# Supplies.net
KiCad netlist of a schematic drawn in Altium Designer
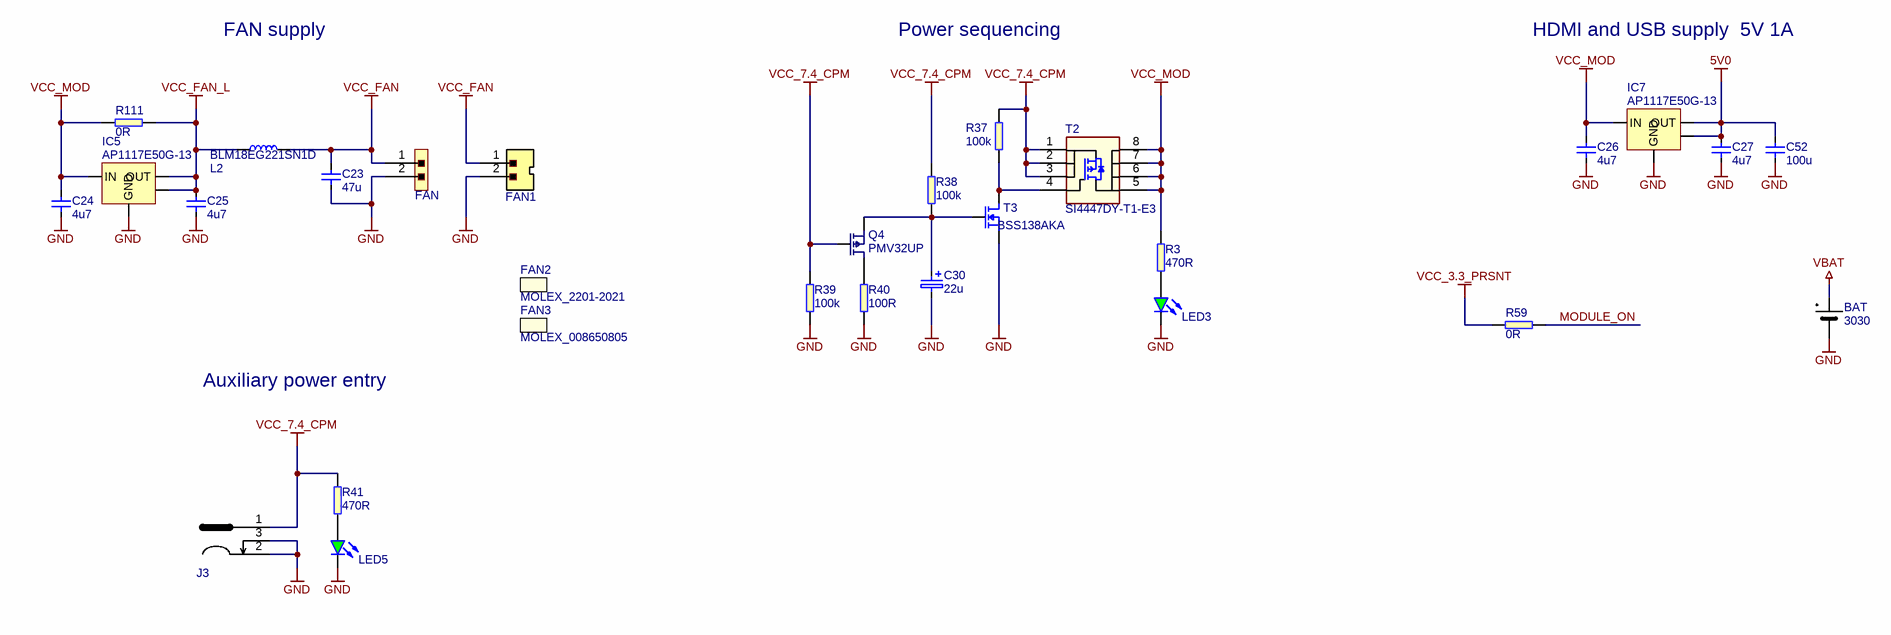
[diagram p0: Supplies.SchDoc]

(export (version "E")
  (design (tool "Eeschema 10.0.6"))
  (components
    (comp (ref "BAT")
      (value "3030")
      (footprint "KEYSTONE_CR1025")
      (description "SMT holder for  CR1025 battery")
      (fields (field (name "MANUFACTURER") "Keystone") (field (name "PART NUMBER") "Keystone_CR1025"))
      (libsource (lib "US-Plus-CPM") (part "battery"))
    )
    (comp (ref "C23")
      (value "47u")
      (footprint "1206")
      (description "MLCC SMT Capacitor 47uF 1206")
      (fields (field (name "PART NUMBER") "C_47u_1206") (field (name "MANUFACTURER") "MURATA"))
      (libsource (lib "US-Plus-CPM") (part "C"))
    )
    (comp (ref "C24")
      (value "4u7")
      (footprint "0603")
      (description "MLCC SMT Capacitor 4u7F 0603")
      (fields (field (name "PART NUMBER") "C_4u7_0603") (field (name "MANUFACTURER") "MULTICOMP"))
      (libsource (lib "US-Plus-CPM") (part "C"))
    )
    (comp (ref "C25")
      (value "4u7")
      (footprint "0603")
      (description "MLCC SMT Capacitor 4u7F 0603")
      (fields (field (name "PART NUMBER") "C_4u7_0603") (field (name "MANUFACTURER") "MULTICOMP"))
      (libsource (lib "US-Plus-CPM") (part "C"))
    )
    (comp (ref "C26")
      (value "4u7")
      (footprint "0603")
      (description "MLCC SMT Capacitor 4u7F 0603")
      (fields (field (name "PART NUMBER") "C_4u7_0603") (field (name "MANUFACTURER") "MULTICOMP"))
      (libsource (lib "US-Plus-CPM") (part "C"))
    )
    (comp (ref "C27")
      (value "4u7")
      (footprint "0603")
      (description "MLCC SMT Capacitor 4u7F 0603")
      (fields (field (name "PART NUMBER") "C_4u7_0603") (field (name "MANUFACTURER") "MULTICOMP"))
      (libsource (lib "US-Plus-CPM") (part "C"))
    )
    (comp (ref "C30")
      (value "22u")
      (footprint "KEMET_C")
      (description "Tantalum SMT Capacitor 22uF Case KEMET_C")
      (fields (field (name "PART NUMBER") "C_22u_KEMET_C") (field (name "MANUFACTURER") "KEMET"))
      (libsource (lib "US-Plus-CPM") (part "CPol"))
    )
    (comp (ref "C52")
      (value "100u")
      (footprint "0805")
      (description "MLCC SMT Capacitor 100uF 0805")
      (fields (field (name "PART NUMBER") "C_100u_0805") (field (name "MANUFACTURER") "MURATA"))
      (libsource (lib "") (part "C_1"))
    )
    (comp (ref "FAN")
      (value "*")
      (footprint "HEADER_1X2_male 2.54mm Angle")
      (description "1x2 pinhead male angle")
      (fields (field (name "PART NUMBER") "HEADER_1X2_male_angle"))
      (libsource (lib "US-Plus-CPM") (part "HEADER_1X2_male_angle"))
    )
    (comp (ref "FAN1")
      (value "MX-22-23-2021")
      (footprint "molex_2223-2021")
      (description "Pinhead connector with key")
      (fields (field (name "PART NUMBER") "molex_2223-2021") (field (name "MANUFACTURER") "Molex"))
      (libsource (lib "US-Plus-CPM") (part "molex_2223-2021"))
    )
    (comp (ref "FAN2")
      (value "MOLEX_2201-2021")
      (description "KK 254 Crimp Housing 2 circuits")
      (fields (field (name "MANUFACTURER") "MOLEX"))
      (libsource (lib "US-Plus-CPM") (part "GENERIC_BOM_ONLY"))
    )
    (comp (ref "FAN3")
      (value "MOLEX_008650805")
      (description "conn term female 22-30 awg tin")
      (fields (field (name "MANUFACTURER") "MOLEX"))
      (libsource (lib "US-Plus-CPM") (part "GENERIC_BOM_ONLY"))
    )
    (comp (ref "IC5")
      (value "AP1117E50G-13")
      (footprint "PCB:SOT223")
      (description "LDO, 2V/5.5V, 1A, 5V,  SOT223")
      (fields (field (name "MANUFACTURER") "Diodes"))
      (libsource (lib "US-Plus-CPM") (part "xx1117"))
    )
    (comp (ref "IC7")
      (value "AP1117E50G-13")
      (footprint "SOT223")
      (description "LDO, 2V/5.5V, 1A, 5V,  SOT223")
      (fields (field (name "MANUFACTURER") "Diodes"))
      (libsource (lib "US-Plus-CPM") (part "xx1117"))
    )
    (comp (ref "J3")
      (value "694106106102")
      (footprint "694106106102")
      (description "DC Power Jack Right Angled SMT Ø6.4 with 4 soldering pads & pegs WR-DC")
      (fields (field (name "PART NUMBER") "WE-694106106102") (field (name "MANUFACTURER") "WURTH ELEKTRONIK"))
      (libsource (lib "US-Plus-CPM") (part "DC_SOCKET_2"))
    )
    (comp (ref "L2")
      (value "BLM18EG221SN1D")
      (footprint "0603")
      (description "MURATA 	BLM18EG221SN1D  FERRITE BEAD, 0.05OHM, 2A, 0603")
      (fields (field (name "MANUFACTURER") "MURATA"))
      (libsource (lib "US-Plus-CPM") (part "Inductor SMT"))
    )
    (comp (ref "LED3")
      (value "KPT-1608SGC")
      (footprint "LED0603")
      (description "LED Green 0603 case")
      (fields (field (name "PART NUMBER") "LED_G") (field (name "MANUFACTURER") "KINGBRIGHT"))
      (libsource (lib "US-Plus-CPM") (part "LED"))
    )
    (comp (ref "LED5")
      (value "KPT-1608SGC")
      (footprint "LED0603")
      (description "LED Green 0603 case")
      (fields (field (name "PART NUMBER") "LED_G") (field (name "MANUFACTURER") "KINGBRIGHT"))
      (libsource (lib "US-Plus-CPM") (part "LED"))
    )
    (comp (ref "Q4")
      (value "PMV32UP")
      (footprint "SOT-23")
      (description "P CH, 20V, 4A")
      (fields (field (name "MANUFACTURER") "NXP"))
      (libsource (lib "US-Plus-CPM") (part "PMOS"))
    )
    (comp (ref "R3")
      (value "470R")
      (footprint "0603")
      (description "SMT Resistor 470R 0603")
      (fields (field (name "PART NUMBER") "R_470R_0603") (field (name "MANUFACTURER") "BOURNS"))
      (libsource (lib "US-Plus-CPM") (part "R"))
    )
    (comp (ref "R37")
      (value "100k")
      (footprint "0603")
      (description "SMT Resistor 100k 0603")
      (fields (field (name "PART NUMBER") "R_100k_0603") (field (name "MANUFACTURER") "BOURNS"))
      (libsource (lib "US-Plus-CPM") (part "R"))
    )
    (comp (ref "R38")
      (value "100k")
      (footprint "0603")
      (description "SMT Resistor 100k 0603")
      (fields (field (name "PART NUMBER") "R_100k_0603") (field (name "MANUFACTURER") "BOURNS"))
      (libsource (lib "US-Plus-CPM") (part "R"))
    )
    (comp (ref "R39")
      (value "100k")
      (footprint "0603")
      (description "SMT Resistor 100k 0603")
      (fields (field (name "PART NUMBER") "R_100k_0603") (field (name "MANUFACTURER") "BOURNS"))
      (libsource (lib "US-Plus-CPM") (part "R"))
    )
    (comp (ref "R40")
      (value "100R")
      (footprint "0603")
      (description "SMT Resistor 100R 0603")
      (fields (field (name "PART NUMBER") "R_100R_0603") (field (name "MANUFACTURER") "MULTICOMP"))
      (libsource (lib "US-Plus-CPM") (part "R"))
    )
    (comp (ref "R41")
      (value "470R")
      (footprint "0603")
      (description "SMT Resistor 470R 0603")
      (fields (field (name "PART NUMBER") "R_470R_0603") (field (name "MANUFACTURER") "BOURNS"))
      (libsource (lib "US-Plus-CPM") (part "R"))
    )
    (comp (ref "R59")
      (value "0R")
      (footprint "0603")
      (description "SMT Resistor 0R 0603")
      (fields (field (name "PART NUMBER") "R_0R_0603") (field (name "MANUFACTURER") "BOURNS"))
      (libsource (lib "") (part "R_1"))
    )
    (comp (ref "R111")
      (value "0R")
      (footprint "0603")
      (description "SMT Resistor 0R 0603")
      (fields (field (name "PART NUMBER") "R_0R_0603") (field (name "MANUFACTURER") "BOURNS"))
      (libsource (lib "") (part "R_1"))
    )
    (comp (ref "T2")
      (value "SI4447DY-T1-E3")
      (footprint "SOIC-SN8_M")
      (description "p-channel MOSFET, SI4447DY-T1-E3")
      (fields (field (name "MANUFACTURER") "VISHAY"))
      (libsource (lib "US-Plus-CPM") (part "SI4447DY-T1-E3"))
    )
    (comp (ref "T3")
      (value "BSS138AKA")
      (footprint "SOT-23")
      (description "MOSFET, N CH, 60V, 0.2A")
      (fields (field (name "PART NUMBER") "BSS138") (field (name "MANUFACTURER") "NXP"))
      (libsource (lib "US-Plus-CPM") (part "NMOS"))
    )
  )
  (nets
    (net (code "1") (name "/MODULE_ON") (class "Default") (node (ref "R59") (pin "2") (pintype "passive")))
    (net (code "2") (name "5V0") (class "Default")
      (node (ref "C27") (pin "2") (pinfunction "2_2") (pintype "passive"))
      (node (ref "C52") (pin "2") (pinfunction "2_2") (pintype "passive"))
      (node (ref "IC7") (pin "2") (pinfunction "OUT_2") (pintype "passive"))
      (node (ref "IC7") (pin "4") (pinfunction "OUT_4") (pintype "passive"))
    )
    (net (code "3") (name "GND") (class "Default")
      (node (ref "BAT") (pin "-") (pinfunction "-_-") (pintype "passive"))
      (node (ref "C23") (pin "1") (pinfunction "1_1") (pintype "passive"))
      (node (ref "C24") (pin "1") (pinfunction "1_1") (pintype "passive"))
      (node (ref "C25") (pin "1") (pinfunction "1_1") (pintype "passive"))
      (node (ref "C26") (pin "1") (pinfunction "1_1") (pintype "passive"))
      (node (ref "C27") (pin "1") (pinfunction "1_1") (pintype "passive"))
      (node (ref "C30") (pin "2") (pinfunction "2_2") (pintype "passive"))
      (node (ref "C52") (pin "1") (pinfunction "1_1") (pintype "passive"))
      (node (ref "FAN") (pin "2") (pinfunction "2_2") (pintype "passive"))
      (node (ref "FAN1") (pin "2") (pinfunction "2_2") (pintype "passive"))
      (node (ref "IC5") (pin "1") (pinfunction "GND_1") (pintype "power_in"))
      (node (ref "IC7") (pin "1") (pinfunction "GND_1") (pintype "power_in"))
      (node (ref "J3") (pin "2") (pinfunction "2_2") (pintype "passive"))
      (node (ref "J3") (pin "3") (pinfunction "3_3") (pintype "passive"))
      (node (ref "LED3") (pin "K") (pinfunction "K_K") (pintype "passive"))
      (node (ref "LED5") (pin "K") (pinfunction "K_K") (pintype "passive"))
      (node (ref "R39") (pin "1") (pintype "passive"))
      (node (ref "R40") (pin "1") (pintype "passive"))
      (node (ref "T3") (pin "2") (pinfunction "S_2") (pintype "passive"))
    )
    (net (code "4") (name "Net-(LED3-PadA)") (class "Default")
      (node (ref "LED3") (pin "A") (pinfunction "A_A") (pintype "passive"))
      (node (ref "R3") (pin "1") (pintype "passive"))
    )
    (net (code "5") (name "Net-(LED5-PadA)") (class "Default")
      (node (ref "LED5") (pin "A") (pinfunction "A_A") (pintype "passive"))
      (node (ref "R41") (pin "1") (pintype "passive"))
    )
    (net (code "6") (name "Net-(Q4-D)") (class "Default")
      (node (ref "Q4") (pin "3") (pinfunction "D_3") (pintype "passive"))
      (node (ref "R40") (pin "2") (pintype "passive"))
    )
    (net (code "7") (name "Net-(Q4-S)") (class "Default")
      (node (ref "C30") (pin "1") (pinfunction "1_1") (pintype "passive"))
      (node (ref "Q4") (pin "2") (pinfunction "S_2") (pintype "passive"))
      (node (ref "R38") (pin "1") (pintype "passive"))
      (node (ref "T3") (pin "1") (pinfunction "G_1") (pintype "passive"))
    )
    (net (code "8") (name "Net-(T3-D)") (class "Default")
      (node (ref "R37") (pin "1") (pintype "passive"))
      (node (ref "T2") (pin "4") (pinfunction "4_4") (pintype "passive"))
      (node (ref "T3") (pin "3") (pinfunction "D_3") (pintype "passive"))
    )
    (net (code "9") (name "VBAT") (class "Default")
      (node (ref "BAT") (pin "+") (pinfunction "+_+") (pintype "passive"))
    )
    (net (code "10") (name "VCC_3.3_PRSNT") (class "Default")
      (node (ref "R59") (pin "1") (pintype "passive"))
    )
    (net (code "11") (name "VCC_7.4_CPM") (class "Default")
      (node (ref "J3") (pin "1") (pinfunction "1_1") (pintype "passive"))
      (node (ref "Q4") (pin "1") (pinfunction "G_1") (pintype "passive"))
      (node (ref "R37") (pin "2") (pintype "passive"))
      (node (ref "R38") (pin "2") (pintype "passive"))
      (node (ref "R39") (pin "2") (pintype "passive"))
      (node (ref "R41") (pin "2") (pintype "passive"))
      (node (ref "T2") (pin "1") (pinfunction "1_1") (pintype "passive"))
      (node (ref "T2") (pin "2") (pinfunction "2_2") (pintype "passive"))
      (node (ref "T2") (pin "3") (pinfunction "3_3") (pintype "passive"))
    )
    (net (code "12") (name "VCC_FAN") (class "Default")
      (node (ref "C23") (pin "2") (pinfunction "2_2") (pintype "passive"))
      (node (ref "FAN") (pin "1") (pinfunction "1_1") (pintype "passive"))
      (node (ref "FAN1") (pin "1") (pinfunction "1_1") (pintype "passive"))
      (node (ref "L2") (pin "2") (pintype "passive"))
    )
    (net (code "13") (name "VCC_FAN_L") (class "Default")
      (node (ref "C25") (pin "2") (pinfunction "2_2") (pintype "passive"))
      (node (ref "IC5") (pin "2") (pinfunction "OUT_2") (pintype "passive"))
      (node (ref "IC5") (pin "4") (pinfunction "OUT_4") (pintype "passive"))
      (node (ref "L2") (pin "1") (pintype "passive"))
      (node (ref "R111") (pin "2") (pintype "passive"))
    )
    (net (code "14") (name "VCC_MOD") (class "Default")
      (node (ref "C24") (pin "2") (pinfunction "2_2") (pintype "passive"))
      (node (ref "C26") (pin "2") (pinfunction "2_2") (pintype "passive"))
      (node (ref "IC5") (pin "3") (pinfunction "IN_3") (pintype "power_in"))
      (node (ref "IC7") (pin "3") (pinfunction "IN_3") (pintype "power_in"))
      (node (ref "R111") (pin "1") (pintype "passive"))
      (node (ref "R3") (pin "2") (pintype "passive"))
      (node (ref "T2") (pin "5") (pinfunction "5_5") (pintype "passive"))
      (node (ref "T2") (pin "6") (pinfunction "6_6") (pintype "passive"))
      (node (ref "T2") (pin "7") (pinfunction "7_7") (pintype "passive"))
      (node (ref "T2") (pin "8") (pinfunction "8_8") (pintype "passive"))
    )
  )
)
